# CPU_LPC1776.net
KiCad netlist of a schematic drawn in Altium Designer
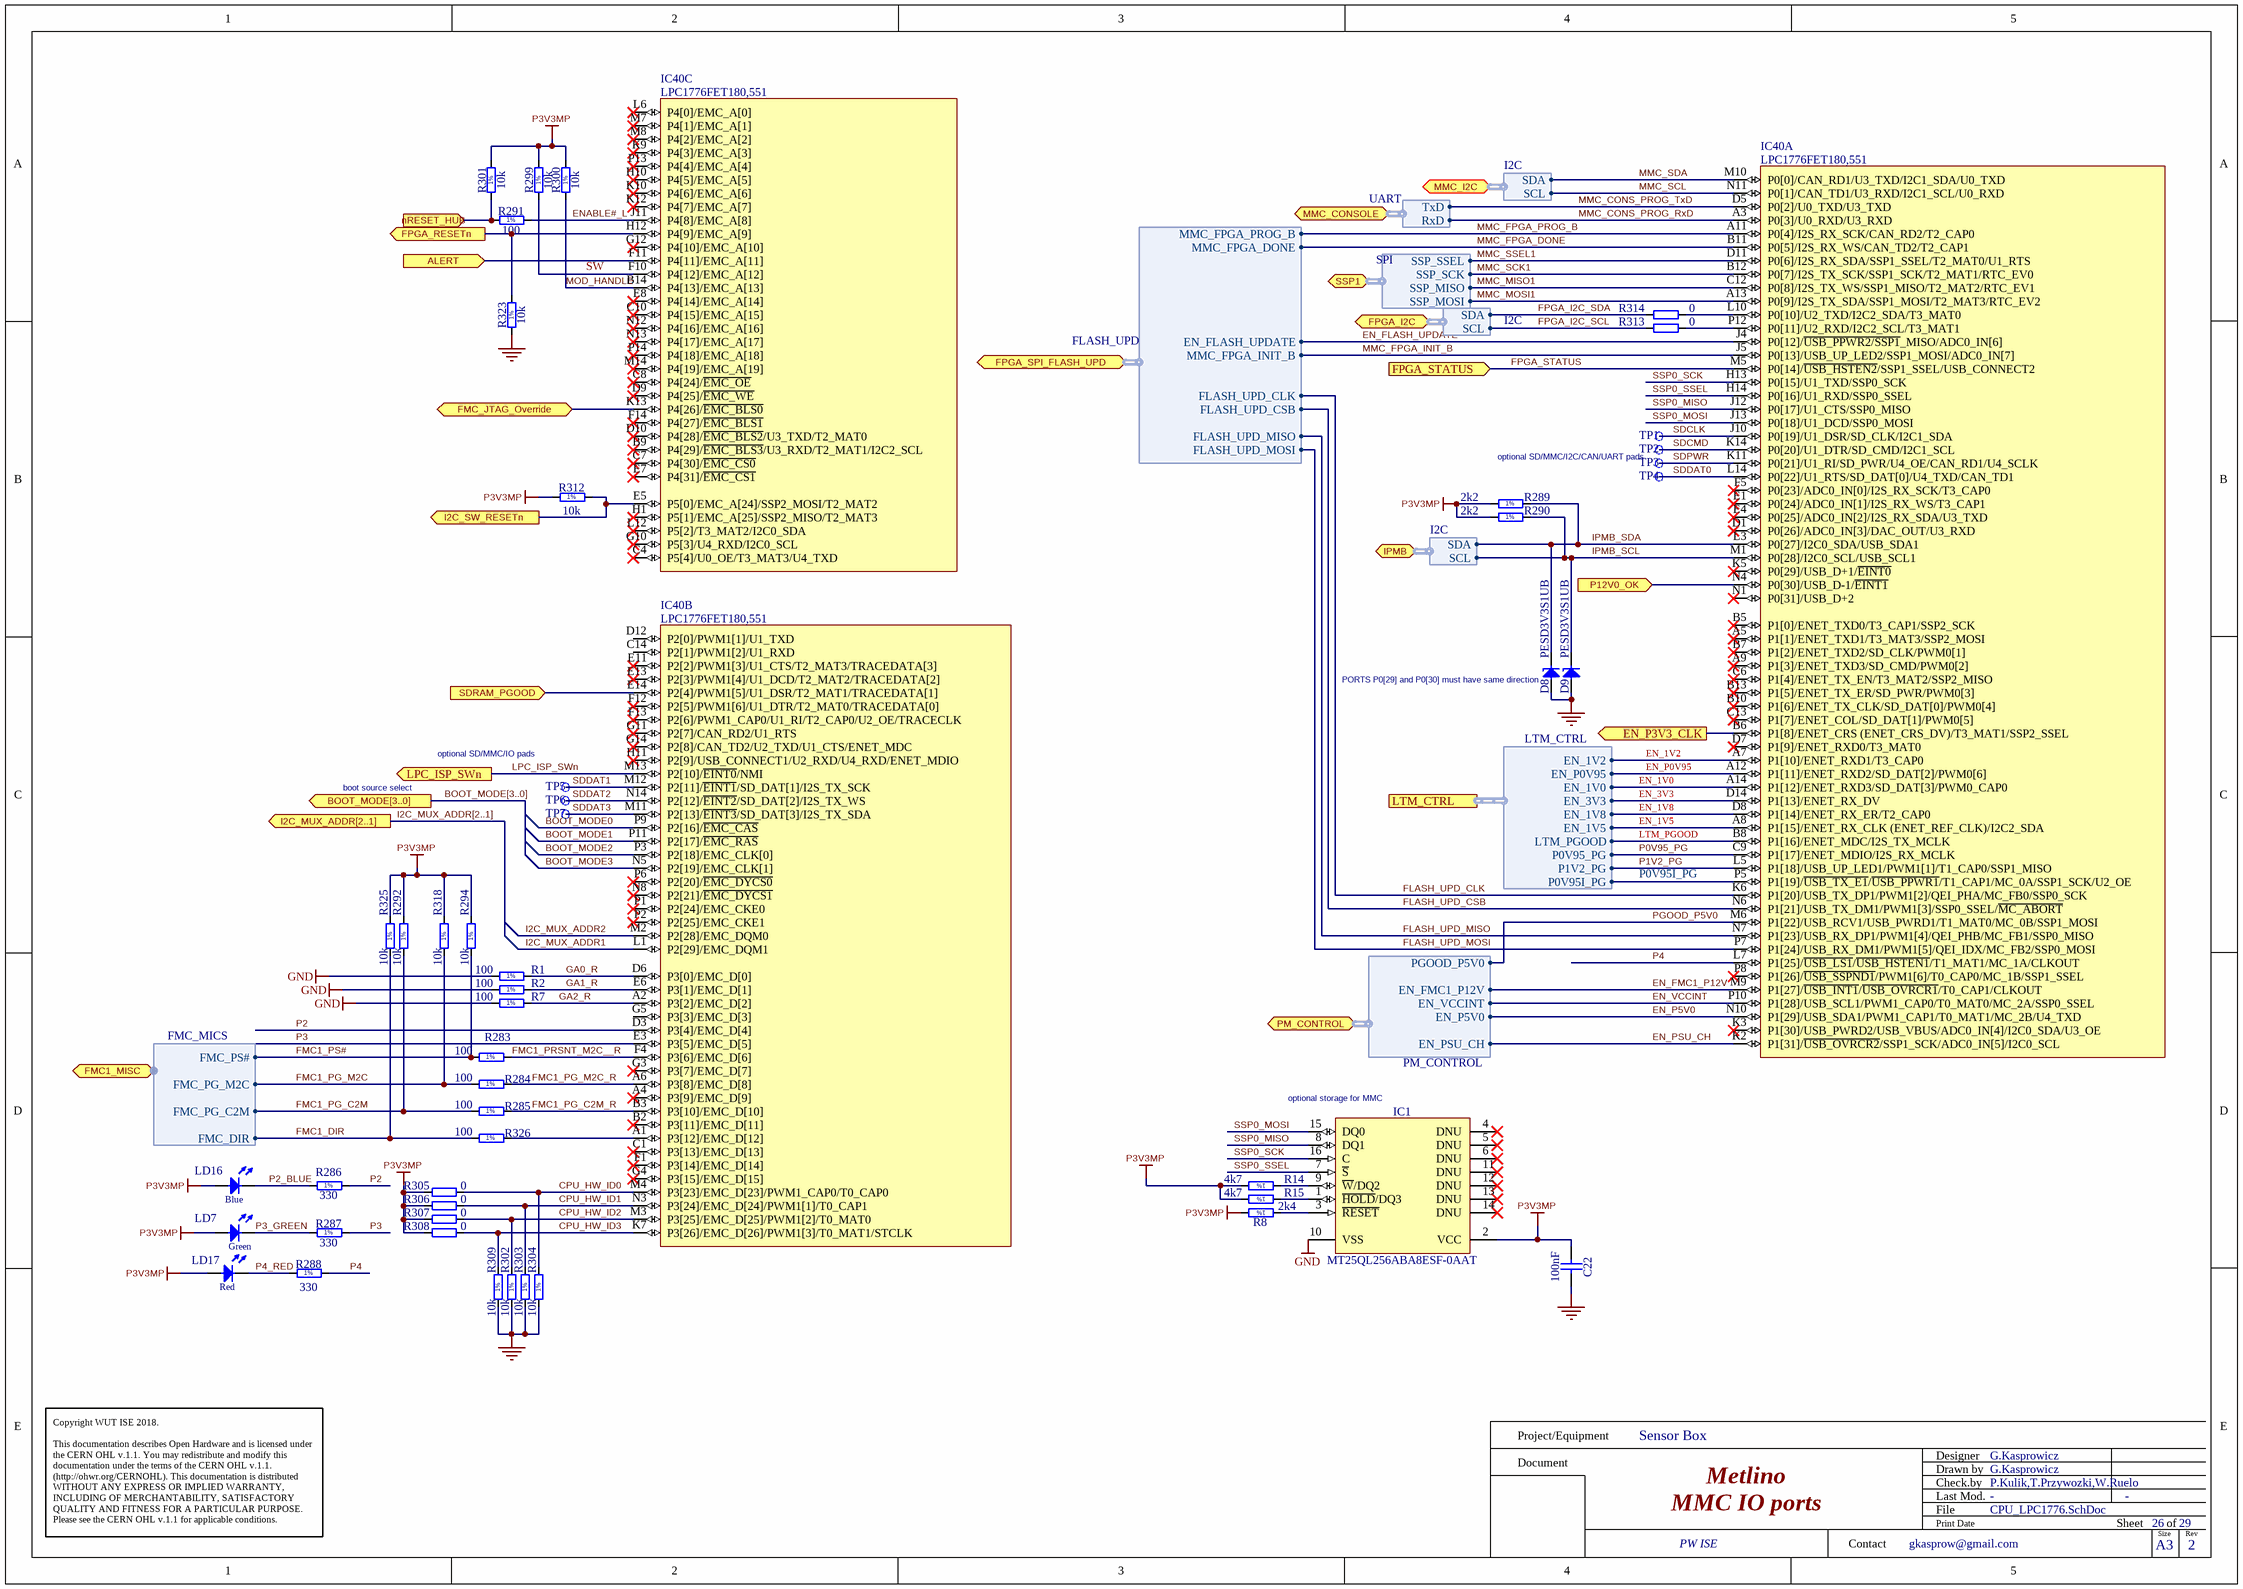
[diagram p0: CPU_LPC1776.SchDoc]

(export (version "E")
  (design (tool "Eeschema 10.0.6"))
  (components
    (comp (ref "C22")
      (value "100nF")
      (footprint "CAPC0603X33N")
      (description "Non-polarised capacitor")
      (fields
        (field (name "MANUFACTURER PART NUMBER") "CC0201_100NF_6.3V_10%_X5R")
        (field (name "MANUFACTURER") "GENERIC")
        (field (name "AUTHOR") "CERN DEM JLC")
      )
      (libsource (lib "Capacitors") (part "Capacitor - non polarized"))
    )
    (comp (ref "D8")
      (value "PESD3V3S1UB")
      (footprint "SODFL1608X65N")
      (description "ESD protection diode")
      (fields
        (field (name "MANUFACTURER") "NXP SEMICONDUCTORS")
        (field (name "VOLTAGE") "3V3")
        (field (name "AUTHOR") "CERN DEM JLC")
      )
      (libsource (lib "ICs And Semiconductors") (part "Diode ESD"))
    )
    (comp (ref "D9")
      (value "PESD3V3S1UB")
      (footprint "SODFL1608X65N")
      (description "ESD protection diode")
      (fields
        (field (name "MANUFACTURER") "NXP SEMICONDUCTORS")
        (field (name "VOLTAGE") "3V3")
        (field (name "AUTHOR") "CERN DEM JLC")
      )
      (libsource (lib "ICs And Semiconductors") (part "Diode ESD"))
    )
    (comp (ref "IC1")
      (value "MT25QL256ABA8ESF-0AAT")
      (footprint "SOIC127P1030X265-16N")
      (description "256Mbit (32MB), 2.7V-3.6V, Multiple I/O Serial NOR Flash Memory,with Reset# & Hold#")
      (fields (field (name "MANUFACTURER") "MICRON TECHNOLOGY") (field (name "AUTHOR") "CERN DEM JLC"))
      (libsource (lib "ICs And Semiconductors") (part "MT25QL256ABA8ESF"))
    )
    (comp (ref "IC40")
      (value "LPC1776FET180,551")
      (footprint "BGA180C80P14X14_1200X1200X120")
      (fields (field (name "MANUFACTURER") "NXP SEMICONDUCTORS") (field (name "AUTHOR") "CERN DEM JMW"))
      (libsource (lib "ICs And Semiconductors") (part "LPC1776FET180,551"))
    )
    (comp (ref "LD7")
      (value "Green")
      (footprint "LED_AVAGO_HSME-C120")
      (description "LED Green 1C 2A")
      (fields
        (field (name "MANUFACTURER PART NUMBER") "HSME-C120")
        (field (name "MANUFACTURER") "AVAGO TECHNOLOGIES")
        (field (name "AUTHOR") "CERN DEM JMW")
      )
      (libsource (lib "ICs And Semiconductors") (part "LED Green 1C 2A"))
    )
    (comp (ref "LD16")
      (value "Blue")
      (footprint "LED_AVAGO_HSMR-C120")
      (description "LED Blue 1C 2A")
      (fields
        (field (name "MANUFACTURER PART NUMBER") "HSMR-C120")
        (field (name "MANUFACTURER") "AVAGO TECHNOLOGIES")
        (field (name "AUTHOR") "CERN DEM JLC")
      )
      (libsource (lib "ICs And Semiconductors") (part "LED Blue 1C 2A"))
    )
    (comp (ref "LD17")
      (value "Red")
      (footprint "LED_KINGBRIGHT_KPH-1608SURCK")
      (description "LED Red 1C 2A")
      (fields
        (field (name "PART NUMBER") "LED_KINGBRIGHT_KPH-1608SURCK")
        (field (name "MANUFACTURER") "KINGBRIGHT")
        (field (name "AUTHOR") "CERN DEM JLC")
      )
      (libsource (lib "ICs And Semiconductors") (part "LED Red 1C 2A"))
    )
    (comp (ref "R1")
      (value "100")
      (footprint "RESC1005X40N")
      (description "Resistor - 1%")
      (fields
        (field (name "MANUFACTURER PART NUMBER") "R0402_100R_1%_0.1W_100PPM_50V")
        (field (name "MANUFACTURER") "GENERIC")
        (field (name "AUTHOR") "CERN DEM JLC")
      )
      (libsource (lib "Resistors") (part "Resistor - 1%"))
    )
    (comp (ref "R2")
      (value "100")
      (footprint "RESC1005X40N")
      (description "Resistor - 1%")
      (fields
        (field (name "MANUFACTURER PART NUMBER") "R0402_100R_1%_0.1W_100PPM_50V")
        (field (name "MANUFACTURER") "GENERIC")
        (field (name "AUTHOR") "CERN DEM JLC")
      )
      (libsource (lib "Resistors") (part "Resistor - 1%"))
    )
    (comp (ref "R7")
      (value "100")
      (footprint "RESC1005X40N")
      (description "Resistor - 1%")
      (fields
        (field (name "MANUFACTURER PART NUMBER") "R0402_100R_1%_0.1W_100PPM_50V")
        (field (name "MANUFACTURER") "GENERIC")
        (field (name "AUTHOR") "CERN DEM JLC")
      )
      (libsource (lib "Resistors") (part "Resistor - 1%"))
    )
    (comp (ref "R8")
      (value "2k4")
      (footprint "RESC1005X40N")
      (description "Resistor - 1%")
      (fields
        (field (name "MANUFACTURER PART NUMBER") "R0402_2K4_1%_0.0625W_100PPM")
        (field (name "MANUFACTURER") "GENERIC")
        (field (name "AUTHOR") "CERN DEM JLC")
      )
      (libsource (lib "Resistors") (part "Resistor - 1%"))
    )
    (comp (ref "R14")
      (value "4k7")
      (footprint "RESC1005X40N")
      (description "Resistor - 1%")
      (fields
        (field (name "MANUFACTURER PART NUMBER") "R0402_4K7_1%_0.0625W_100PPM")
        (field (name "MANUFACTURER") "GENERIC")
        (field (name "AUTHOR") "CERN DEM JLC")
      )
      (libsource (lib "Resistors") (part "Resistor - 1%"))
    )
    (comp (ref "R15")
      (value "4k7")
      (footprint "RESC1005X40N")
      (description "Resistor - 1%")
      (fields
        (field (name "MANUFACTURER PART NUMBER") "R0402_4K7_1%_0.0625W_100PPM")
        (field (name "MANUFACTURER") "GENERIC")
        (field (name "AUTHOR") "CERN DEM JLC")
      )
      (libsource (lib "Resistors") (part "Resistor - 1%"))
    )
    (comp (ref "R283")
      (value "100")
      (footprint "RESC1005X40N")
      (description "Resistor - 1%")
      (fields
        (field (name "MANUFACTURER PART NUMBER") "R0402_100R_1%_0.1W_100PPM_50V")
        (field (name "MANUFACTURER") "GENERIC")
        (field (name "AUTHOR") "CERN DEM JLC")
      )
      (libsource (lib "Resistors") (part "Resistor - 1%"))
    )
    (comp (ref "R284")
      (value "100")
      (footprint "RESC1005X40N")
      (description "Resistor - 1%")
      (fields
        (field (name "MANUFACTURER PART NUMBER") "R0402_100R_1%_0.1W_100PPM_50V")
        (field (name "MANUFACTURER") "GENERIC")
        (field (name "AUTHOR") "CERN DEM JLC")
      )
      (libsource (lib "Resistors") (part "Resistor - 1%"))
    )
    (comp (ref "R285")
      (value "100")
      (footprint "RESC1005X40N")
      (description "Resistor - 1%")
      (fields
        (field (name "MANUFACTURER PART NUMBER") "R0402_100R_1%_0.1W_100PPM_50V")
        (field (name "MANUFACTURER") "GENERIC")
        (field (name "AUTHOR") "CERN DEM JLC")
      )
      (libsource (lib "Resistors") (part "Resistor - 1%"))
    )
    (comp (ref "R286")
      (value "330")
      (footprint "RESC1005X40N")
      (description "Resistor - 1%")
      (fields
        (field (name "MANUFACTURER PART NUMBER") "R0402_330R_1%_0.0625W_100PPM")
        (field (name "MANUFACTURER") "GENERIC")
        (field (name "AUTHOR") "CERN DEM JLC")
      )
      (libsource (lib "Resistors") (part "Resistor - 1%"))
    )
    (comp (ref "R287")
      (value "330")
      (footprint "RESC1005X40N")
      (description "Resistor - 1%")
      (fields
        (field (name "MANUFACTURER PART NUMBER") "R0402_330R_1%_0.0625W_100PPM")
        (field (name "MANUFACTURER") "GENERIC")
        (field (name "AUTHOR") "CERN DEM JLC")
      )
      (libsource (lib "Resistors") (part "Resistor - 1%"))
    )
    (comp (ref "R288")
      (value "330")
      (footprint "RESC1005X40N")
      (description "Resistor - 1%")
      (fields
        (field (name "MANUFACTURER PART NUMBER") "R0402_330R_1%_0.0625W_100PPM")
        (field (name "MANUFACTURER") "GENERIC")
        (field (name "AUTHOR") "CERN DEM JLC")
      )
      (libsource (lib "Resistors") (part "Resistor - 1%"))
    )
    (comp (ref "R289")
      (value "2k2")
      (footprint "RESC1005X40N")
      (description "Resistor - 1%")
      (fields
        (field (name "MANUFACTURER PART NUMBER") "R0402_2K2_1%_0.0625W_100PPM")
        (field (name "MANUFACTURER") "GENERIC")
        (field (name "AUTHOR") "CERN DEM JLC")
      )
      (libsource (lib "Resistors") (part "Resistor - 1%"))
    )
    (comp (ref "R290")
      (value "2k2")
      (footprint "RESC1005X40N")
      (description "Resistor - 1%")
      (fields
        (field (name "MANUFACTURER PART NUMBER") "R0402_2K2_1%_0.0625W_100PPM")
        (field (name "MANUFACTURER") "GENERIC")
        (field (name "AUTHOR") "CERN DEM JLC")
      )
      (libsource (lib "Resistors") (part "Resistor - 1%"))
    )
    (comp (ref "R291")
      (value "100")
      (footprint "RESC1005X40N")
      (description "Resistor - 1%")
      (fields
        (field (name "MANUFACTURER PART NUMBER") "R0402_100R_1%_0.1W_100PPM_50V")
        (field (name "MANUFACTURER") "GENERIC")
        (field (name "AUTHOR") "CERN DEM JLC")
      )
      (libsource (lib "Resistors") (part "Resistor - 1%"))
    )
    (comp (ref "R292")
      (value "10k")
      (footprint "RESC1005X40N")
      (description "Resistor - 1%")
      (fields
        (field (name "MANUFACTURER PART NUMBER") "R0402_10K_1%_0.0625W_100PPM")
        (field (name "MANUFACTURER") "GENERIC")
        (field (name "AUTHOR") "CERN DEM JLC")
      )
      (libsource (lib "Resistors") (part "Resistor - 1%"))
    )
    (comp (ref "R294")
      (value "10k")
      (footprint "RESC1005X40N")
      (description "Resistor - 1%")
      (fields
        (field (name "MANUFACTURER PART NUMBER") "R0402_10K_1%_0.0625W_100PPM")
        (field (name "MANUFACTURER") "GENERIC")
        (field (name "AUTHOR") "CERN DEM JLC")
      )
      (libsource (lib "Resistors") (part "Resistor - 1%"))
    )
    (comp (ref "R299")
      (value "10k")
      (footprint "RESC1005X40N")
      (description "Resistor - 1%")
      (fields
        (field (name "MANUFACTURER PART NUMBER") "R0402_10K_1%_0.0625W_100PPM")
        (field (name "MANUFACTURER") "GENERIC")
        (field (name "AUTHOR") "CERN DEM JLC")
      )
      (libsource (lib "Resistors") (part "Resistor - 1%"))
    )
    (comp (ref "R300")
      (value "10k")
      (footprint "RESC1005X40N")
      (description "Resistor - 1%")
      (fields
        (field (name "MANUFACTURER PART NUMBER") "R0402_10K_1%_0.0625W_100PPM")
        (field (name "MANUFACTURER") "GENERIC")
        (field (name "AUTHOR") "CERN DEM JLC")
      )
      (libsource (lib "Resistors") (part "Resistor - 1%"))
    )
    (comp (ref "R301")
      (value "10k")
      (footprint "RESC1005X40N")
      (description "Resistor - 1%")
      (fields
        (field (name "MANUFACTURER PART NUMBER") "R0402_10K_1%_0.0625W_100PPM")
        (field (name "MANUFACTURER") "GENERIC")
        (field (name "AUTHOR") "CERN DEM JLC")
      )
      (libsource (lib "Resistors") (part "Resistor - 1%"))
    )
    (comp (ref "R302")
      (value "10k")
      (footprint "RESC1005X40N")
      (description "Resistor - 1%")
      (fields
        (field (name "MANUFACTURER PART NUMBER") "R0402_10K_1%_0.0625W_100PPM")
        (field (name "MANUFACTURER") "GENERIC")
        (field (name "AUTHOR") "CERN DEM JLC")
      )
      (libsource (lib "Resistors") (part "Resistor - 1%"))
    )
    (comp (ref "R303")
      (value "10k")
      (footprint "RESC1005X40N")
      (description "Resistor - 1%")
      (fields
        (field (name "MANUFACTURER PART NUMBER") "R0402_10K_1%_0.0625W_100PPM")
        (field (name "MANUFACTURER") "GENERIC")
        (field (name "AUTHOR") "CERN DEM JLC")
      )
      (libsource (lib "Resistors") (part "Resistor - 1%"))
    )
    (comp (ref "R304")
      (value "10k")
      (footprint "RESC1005X40N")
      (description "Resistor - 1%")
      (fields
        (field (name "MANUFACTURER PART NUMBER") "R0402_10K_1%_0.0625W_100PPM")
        (field (name "MANUFACTURER") "GENERIC")
        (field (name "AUTHOR") "CERN DEM JLC")
      )
      (libsource (lib "Resistors") (part "Resistor - 1%"))
    )
    (comp (ref "R305")
      (value "0")
      (footprint "RESC1005X40N")
      (description "Resistor")
      (fields
        (field (name "MANUFACTURER PART NUMBER") "R0402_0R_JUMPER")
        (field (name "MANUFACTURER") "GENERIC")
        (field (name "AUTHOR") "CERN DEM JLC")
      )
      (libsource (lib "Resistors") (part "Resistor"))
    )
    (comp (ref "R306")
      (value "0")
      (footprint "RESC1005X40N")
      (description "Resistor")
      (fields
        (field (name "MANUFACTURER PART NUMBER") "R0402_0R_JUMPER")
        (field (name "MANUFACTURER") "GENERIC")
        (field (name "AUTHOR") "CERN DEM JLC")
      )
      (libsource (lib "Resistors") (part "Resistor"))
    )
    (comp (ref "R307")
      (value "0")
      (footprint "RESC1005X40N")
      (description "Resistor")
      (fields
        (field (name "MANUFACTURER PART NUMBER") "R0402_0R_JUMPER")
        (field (name "MANUFACTURER") "GENERIC")
        (field (name "AUTHOR") "CERN DEM JLC")
      )
      (libsource (lib "Resistors") (part "Resistor"))
    )
    (comp (ref "R308")
      (value "0")
      (footprint "RESC1005X40N")
      (description "Resistor")
      (fields
        (field (name "MANUFACTURER PART NUMBER") "R0402_0R_JUMPER")
        (field (name "MANUFACTURER") "GENERIC")
        (field (name "AUTHOR") "CERN DEM JLC")
      )
      (libsource (lib "Resistors") (part "Resistor"))
    )
    (comp (ref "R309")
      (value "10k")
      (footprint "RESC1005X40N")
      (description "Resistor - 1%")
      (fields
        (field (name "MANUFACTURER PART NUMBER") "R0402_10K_1%_0.0625W_100PPM")
        (field (name "MANUFACTURER") "GENERIC")
        (field (name "AUTHOR") "CERN DEM JLC")
      )
      (libsource (lib "Resistors") (part "Resistor - 1%"))
    )
    (comp (ref "R312")
      (value "10k")
      (footprint "RESC1005X40N")
      (description "Resistor - 1%")
      (fields
        (field (name "MANUFACTURER PART NUMBER") "R0402_10K_1%_0.0625W_100PPM")
        (field (name "MANUFACTURER") "GENERIC")
        (field (name "AUTHOR") "CERN DEM JLC")
      )
      (libsource (lib "Resistors") (part "Resistor - 1%"))
    )
    (comp (ref "R313")
      (value "0")
      (footprint "RESC1005X40N")
      (description "Resistor")
      (fields
        (field (name "MANUFACTURER PART NUMBER") "R0402_0R_JUMPER")
        (field (name "MANUFACTURER") "GENERIC")
        (field (name "AUTHOR") "CERN DEM JLC")
      )
      (libsource (lib "Resistors") (part "Resistor"))
    )
    (comp (ref "R314")
      (value "0")
      (footprint "RESC1005X40N")
      (description "Resistor")
      (fields
        (field (name "MANUFACTURER PART NUMBER") "R0402_0R_JUMPER")
        (field (name "MANUFACTURER") "GENERIC")
        (field (name "AUTHOR") "CERN DEM JLC")
      )
      (libsource (lib "Resistors") (part "Resistor"))
    )
    (comp (ref "R318")
      (value "10k")
      (footprint "RESC1005X40N")
      (description "Resistor - 1%")
      (fields
        (field (name "MANUFACTURER PART NUMBER") "R0402_10K_1%_0.0625W_100PPM")
        (field (name "MANUFACTURER") "GENERIC")
        (field (name "AUTHOR") "CERN DEM JLC")
      )
      (libsource (lib "Resistors") (part "Resistor - 1%"))
    )
    (comp (ref "R323")
      (value "10k")
      (footprint "RESC1005X40N")
      (description "Resistor - 1%")
      (fields
        (field (name "MANUFACTURER PART NUMBER") "R0402_10K_1%_0.0625W_100PPM")
        (field (name "MANUFACTURER") "GENERIC")
        (field (name "AUTHOR") "CERN DEM JLC")
      )
      (libsource (lib "Resistors") (part "Resistor - 1%"))
    )
    (comp (ref "R325")
      (value "10k")
      (footprint "RESC1005X40N")
      (description "Resistor - 1%")
      (fields
        (field (name "MANUFACTURER PART NUMBER") "R0402_10K_1%_0.0625W_100PPM")
        (field (name "MANUFACTURER") "GENERIC")
        (field (name "AUTHOR") "CERN DEM JLC")
      )
      (libsource (lib "Resistors") (part "Resistor - 1%"))
    )
    (comp (ref "R326")
      (value "100")
      (footprint "RESC1005X40N")
      (description "Resistor - 1%")
      (fields
        (field (name "MANUFACTURER PART NUMBER") "R0402_100R_1%_0.1W_100PPM_50V")
        (field (name "MANUFACTURER") "GENERIC")
        (field (name "AUTHOR") "CERN DEM JLC")
      )
      (libsource (lib "Resistors") (part "Resistor - 1%"))
    )
    (comp (ref "TP1")
      (value "SMD_PAD_D1MM")
      (footprint "C100")
      (libsource (lib "altium-import") (part "root_0__*"))
    )
    (comp (ref "TP2")
      (value "SMD_PAD_D1MM")
      (footprint "C100")
      (libsource (lib "altium-import") (part "root_0__*"))
    )
    (comp (ref "TP3")
      (value "SMD_PAD_D1MM")
      (footprint "C100")
      (libsource (lib "altium-import") (part "root_0__*"))
    )
    (comp (ref "TP4")
      (value "SMD_PAD_D1MM")
      (footprint "C100")
      (libsource (lib "altium-import") (part "root_0__*"))
    )
    (comp (ref "TP5")
      (value "SMD_PAD_D1MM")
      (footprint "C100")
      (libsource (lib "altium-import") (part "root_0__*"))
    )
    (comp (ref "TP6")
      (value "SMD_PAD_D1MM")
      (footprint "C100")
      (libsource (lib "altium-import") (part "root_0__*"))
    )
    (comp (ref "TP7")
      (value "SMD_PAD_D1MM")
      (footprint "C100")
      (libsource (lib "altium-import") (part "root_0__*"))
    )
  )
  (nets
    (net (code "8") (name "/ALERT") (class "Default")
      (node (ref "IC40") (pin "F11") (pinfunction "P4[11]/EMC_A[11]_F11") (pintype "bidirectional"))
    )
    (net (code "9") (name "/BOOT_MODE0") (class "Default")
      (node (ref "IC40") (pin "P9") (pinfunction "P2[16]/~{EMC_CAS}_P9") (pintype "bidirectional"))
    )
    (net (code "10") (name "/BOOT_MODE1") (class "Default")
      (node (ref "IC40") (pin "P11") (pinfunction "P2[17]/~{EMC_RAS}_P11") (pintype "bidirectional"))
    )
    (net (code "11") (name "/BOOT_MODE2") (class "Default")
      (node (ref "IC40") (pin "P3") (pinfunction "P2[18]/EMC_CLK[0]_P3") (pintype "bidirectional"))
    )
    (net (code "12") (name "/BOOT_MODE3") (class "Default")
      (node (ref "IC40") (pin "N5") (pinfunction "P2[19]/EMC_CLK[1]_N5") (pintype "bidirectional"))
    )
    (net (code "14") (name "/CPU_HW_ID0") (class "Default")
      (node (ref "IC40") (pin "M4") (pinfunction "P3[23]/EMC_D[23]/PWM1_CAP0/T0_CAP0_M4") (pintype "bidirectional"))
      (node (ref "R304") (pin "2") (pinfunction "2_2") (pintype "passive"))
      (node (ref "R305") (pin "2") (pinfunction "2_2") (pintype "passive"))
    )
    (net (code "15") (name "/CPU_HW_ID1") (class "Default")
      (node (ref "IC40") (pin "N3") (pinfunction "P3[24]/EMC_D[24]/PWM1[1]/T0_CAP1_N3") (pintype "bidirectional"))
      (node (ref "R303") (pin "2") (pinfunction "2_2") (pintype "passive"))
      (node (ref "R306") (pin "2") (pinfunction "2_2") (pintype "passive"))
    )
    (net (code "16") (name "/CPU_HW_ID2") (class "Default")
      (node (ref "IC40") (pin "M3") (pinfunction "P3[25]/EMC_D[25]/PWM1[2]/T0_MAT0_M3") (pintype "bidirectional"))
      (node (ref "R302") (pin "2") (pinfunction "2_2") (pintype "passive"))
      (node (ref "R307") (pin "2") (pinfunction "2_2") (pintype "passive"))
    )
    (net (code "17") (name "/CPU_HW_ID3") (class "Default")
      (node (ref "IC40") (pin "K7") (pinfunction "P3[26]/EMC_D[26]/PWM1[3]/T0_MAT1/STCLK_K7") (pintype "bidirectional"))
      (node (ref "R308") (pin "2") (pinfunction "2_2") (pintype "passive"))
      (node (ref "R309") (pin "2") (pinfunction "2_2") (pintype "passive"))
    )
    (net (code "18") (name "/ENABLE#_L") (class "Default")
      (node (ref "IC40") (pin "J11") (pinfunction "P4[8]/EMC_A[8]_J11") (pintype "bidirectional"))
      (node (ref "R291") (pin "2") (pinfunction "2_2") (pintype "passive"))
    )
    (net (code "19") (name "/EN_1V0") (class "Default")
      (node (ref "IC40") (pin "A14") (pinfunction "P1[12]/ENET_RXD3/SD_DAT[3]/PWM0_CAP0_A14") (pintype "bidirectional"))
    )
    (net (code "20") (name "/EN_1V2") (class "Default")
      (node (ref "IC40") (pin "A7") (pinfunction "P1[10]/ENET_RXD1/T3_CAP0_A7") (pintype "bidirectional"))
    )
    (net (code "21") (name "/EN_1V5") (class "Default")
      (node (ref "IC40") (pin "A8") (pinfunction "P1[15]/ENET_RX_CLK_(ENET_REF_CLK)/I2C2_SDA_A8") (pintype "bidirectional"))
    )
    (net (code "22") (name "/EN_1V8") (class "Default")
      (node (ref "IC40") (pin "D8") (pinfunction "P1[14]/ENET_RX_ER/T2_CAP0_D8") (pintype "bidirectional"))
    )
    (net (code "23") (name "/EN_3V3") (class "Default")
      (node (ref "IC40") (pin "D14") (pinfunction "P1[13]/ENET_RX_DV_D14") (pintype "bidirectional"))
    )
    (net (code "24") (name "/EN_FLASH_UPDATE") (class "Default")
      (node (ref "IC40") (pin "J4") (pinfunction "P0[12]/~{USB_PPWR2/SSP1}_MISO/ADC0_IN[6]_J4") (pintype "bidirectional"))
    )
    (net (code "25") (name "/EN_FMC1_P12V") (class "Default")
      (node (ref "IC40") (pin "M9") (pinfunction "P1[27]/~{USB_INT1}/~{USB_OVRCR1}/T0_CAP1/CLKOUT_M9") (pintype "bidirectional"))
    )
    (net (code "26") (name "/EN_P0V95") (class "Default")
      (node (ref "IC40") (pin "A12") (pinfunction "P1[11]/ENET_RXD2/SD_DAT[2]/PWM0[6]_A12") (pintype "bidirectional"))
    )
    (net (code "27") (name "/EN_P3V3_CLK") (class "Default")
      (node (ref "IC40") (pin "B6") (pinfunction "P1[8]/ENET_CRS_(ENET_CRS_DV)/T3_MAT1/SSP2_SSEL_B6") (pintype "bidirectional"))
    )
    (net (code "28") (name "/EN_P5V0") (class "Default")
      (node (ref "IC40") (pin "N10") (pinfunction "P1[29]/USB_SDA1/PWM1_CAP1/T0_MAT1/MC_2B/U4_TXD_N10") (pintype "bidirectional"))
    )
    (net (code "29") (name "/EN_PSU_CH") (class "Default")
      (node (ref "IC40") (pin "K2") (pinfunction "P1[31]/~{USB_OVRCR2}/SSP1_SCK/ADC0_IN[5]/I2C0_SCL_K2") (pintype "bidirectional"))
    )
    (net (code "30") (name "/EN_VCCINT") (class "Default")
      (node (ref "IC40") (pin "P10") (pinfunction "P1[28]/USB_SCL1/PWM1_CAP0/T0_MAT0/MC_2A/SSP0_SSEL_P10") (pintype "bidirectional"))
    )
    (net (code "31") (name "/FLASH_UPD_CLK") (class "Default")
      (node (ref "IC40") (pin "K6") (pinfunction "P1[20]/USB_TX_DP1/PWM1[2]/QEI_PHA/MC_FB0/SSP0_SCK_K6") (pintype "bidirectional"))
    )
    (net (code "32") (name "/FLASH_UPD_CSB") (class "Default")
      (node (ref "IC40") (pin "N6") (pinfunction "P1[21]/USB_TX_DM1/PWM1[3]/SSP0_SSEL/~{MC_ABORT}_N6") (pintype "bidirectional"))
    )
    (net (code "33") (name "/FLASH_UPD_MISO") (class "Default")
      (node (ref "IC40") (pin "N7") (pinfunction "P1[23]/USB_RX_DP1/PWM1[4]/QEI_PHB/MC_FB1/SSP0_MISO_N7") (pintype "bidirectional"))
    )
    (net (code "34") (name "/FLASH_UPD_MOSI") (class "Default")
      (node (ref "IC40") (pin "P7") (pinfunction "P1[24]/USB_RX_DM1/PWM1[5]/QEI_IDX/MC_FB2/SSP0_MOSI_P7") (pintype "bidirectional"))
    )
    (net (code "35") (name "/FMC1_DIR") (class "Default")
      (node (ref "R325") (pin "1") (pinfunction "1_1") (pintype "passive"))
      (node (ref "R326") (pin "1") (pinfunction "1_1") (pintype "passive"))
    )
    (net (code "36") (name "/FMC1_PG_C2M") (class "Default")
      (node (ref "R285") (pin "1") (pinfunction "1_1") (pintype "passive"))
      (node (ref "R292") (pin "1") (pinfunction "1_1") (pintype "passive"))
    )
    (net (code "37") (name "/FMC1_PG_C2M_R") (class "Default")
      (node (ref "IC40") (pin "B3") (pinfunction "P3[10]/EMC_D[10]_B3") (pintype "bidirectional"))
      (node (ref "R285") (pin "2") (pinfunction "2_2") (pintype "passive"))
    )
    (net (code "38") (name "/FMC1_PG_M2C") (class "Default")
      (node (ref "R284") (pin "1") (pinfunction "1_1") (pintype "passive"))
      (node (ref "R318") (pin "1") (pinfunction "1_1") (pintype "passive"))
    )
    (net (code "39") (name "/FMC1_PG_M2C_R") (class "Default")
      (node (ref "IC40") (pin "A6") (pinfunction "P3[8]/EMC_D[8]_A6") (pintype "bidirectional"))
      (node (ref "R284") (pin "2") (pinfunction "2_2") (pintype "passive"))
    )
    (net (code "40") (name "/FMC1_PRSNT_M2C__R") (class "Default")
      (node (ref "IC40") (pin "F4") (pinfunction "P3[6]/EMC_D[6]_F4") (pintype "bidirectional"))
      (node (ref "R283") (pin "2") (pinfunction "2_2") (pintype "passive"))
    )
    (net (code "41") (name "/FMC1_PS#") (class "Default")
      (node (ref "R283") (pin "1") (pinfunction "1_1") (pintype "passive"))
      (node (ref "R294") (pin "1") (pinfunction "1_1") (pintype "passive"))
    )
    (net (code "42") (name "/FMC_JTAG_Override") (class "Default")
      (node (ref "IC40") (pin "K13") (pinfunction "P4[26]/~{EMC_BLS0}_K13") (pintype "bidirectional"))
    )
    (net (code "43") (name "/FPGA_I2C_SCL") (class "Default")
      (node (ref "R313") (pin "1") (pinfunction "1_1") (pintype "passive"))
    )
    (net (code "44") (name "/FPGA_I2C_SDA") (class "Default")
      (node (ref "R314") (pin "1") (pinfunction "1_1") (pintype "passive"))
    )
    (net (code "45") (name "/FPGA_RESETn") (class "Default")
      (node (ref "IC40") (pin "H12") (pinfunction "P4[9]/EMC_A[9]_H12") (pintype "bidirectional"))
      (node (ref "R323") (pin "2") (pinfunction "2_2") (pintype "passive"))
    )
    (net (code "46") (name "/FPGA_STATUS") (class "Default")
      (node (ref "IC40") (pin "M5") (pinfunction "P0[14]/~{USB_HSTEN2}/SSP1_SSEL/USB_CONNECT2_M5") (pintype "bidirectional"))
    )
    (net (code "47") (name "/GA0_R") (class "Default")
      (node (ref "IC40") (pin "D6") (pinfunction "P3[0]/EMC_D[0]_D6") (pintype "bidirectional"))
      (node (ref "R1") (pin "2") (pinfunction "2_2") (pintype "passive"))
    )
    (net (code "48") (name "/GA1_R") (class "Default")
      (node (ref "IC40") (pin "E6") (pinfunction "P3[1]/EMC_D[1]_E6") (pintype "bidirectional"))
      (node (ref "R2") (pin "2") (pinfunction "2_2") (pintype "passive"))
    )
    (net (code "49") (name "/GA2_R") (class "Default")
      (node (ref "IC40") (pin "A2") (pinfunction "P3[2]/EMC_D[2]_A2") (pintype "bidirectional"))
      (node (ref "R7") (pin "2") (pinfunction "2_2") (pintype "passive"))
    )
    (net (code "50") (name "/I2C_MUX_ADDR1") (class "Default")
      (node (ref "IC40") (pin "L1") (pinfunction "P2[29]/EMC_DQM1_L1") (pintype "bidirectional"))
    )
    (net (code "51") (name "/I2C_MUX_ADDR2") (class "Default")
      (node (ref "IC40") (pin "M2") (pinfunction "P2[28]/EMC_DQM0_M2") (pintype "bidirectional"))
    )
    (net (code "53") (name "/I2C_SW_RESETn") (class "Default")
      (node (ref "IC40") (pin "E5") (pinfunction "P5[0]/EMC_A[24]/SSP2_MOSI/T2_MAT2_E5") (pintype "bidirectional"))
      (node (ref "R312") (pin "2") (pinfunction "2_2") (pintype "passive"))
    )
    (net (code "54") (name "/IPMB_SCL") (class "Default")
      (node (ref "D9") (pin "1") (pinfunction "C_1") (pintype "passive"))
      (node (ref "IC40") (pin "M1") (pinfunction "P0[28]/I2C0_SCL/USB_SCL1_M1") (pintype "bidirectional"))
      (node (ref "R290") (pin "2") (pinfunction "2_2") (pintype "passive"))
    )
    (net (code "55") (name "/IPMB_SDA") (class "Default")
      (node (ref "D8") (pin "1") (pinfunction "C_1") (pintype "passive"))
      (node (ref "IC40") (pin "L3") (pinfunction "P0[27]/I2C0_SDA/USB_SDA1_L3") (pintype "bidirectional"))
      (node (ref "R289") (pin "2") (pinfunction "2_2") (pintype "passive"))
    )
    (net (code "56") (name "/LPC_ISP_SWn") (class "Default")
      (node (ref "IC40") (pin "M13") (pinfunction "P2[10]/~{EINT0}/NMI_M13") (pintype "bidirectional"))
    )
    (net (code "57") (name "/LTM_PGOOD") (class "Default")
      (node (ref "IC40") (pin "B8") (pinfunction "P1[16]/ENET_MDC/I2S_TX_MCLK_B8") (pintype "bidirectional"))
    )
    (net (code "58") (name "/MMC_CONS_PROG_RxD") (class "Default")
      (node (ref "IC40") (pin "A3") (pinfunction "P0[3]/U0_RXD/U3_RXD_A3") (pintype "bidirectional"))
    )
    (net (code "59") (name "/MMC_CONS_PROG_TxD") (class "Default")
      (node (ref "IC40") (pin "D5") (pinfunction "P0[2]/U0_TXD/U3_TXD_D5") (pintype "bidirectional"))
    )
    (net (code "60") (name "/MMC_FPGA_DONE") (class "Default")
      (node (ref "IC40") (pin "B11") (pinfunction "P0[5]/I2S_RX_WS/CAN_TD2/T2_CAP1_B11") (pintype "bidirectional"))
    )
    (net (code "61") (name "/MMC_FPGA_INIT_B") (class "Default")
      (node (ref "IC40") (pin "J5") (pinfunction "P0[13]/USB_UP_LED2/SSP1_MOSI/ADC0_IN[7]_J5") (pintype "bidirectional"))
    )
    (net (code "62") (name "/MMC_FPGA_PROG_B") (class "Default")
      (node (ref "IC40") (pin "A11") (pinfunction "P0[4]/I2S_RX_SCK/CAN_RD2/T2_CAP0_A11") (pintype "bidirectional"))
    )
    (net (code "63") (name "/MMC_MISO1") (class "Default")
      (node (ref "IC40") (pin "C12") (pinfunction "P0[8]/I2S_TX_WS/SSP1_MISO/T2_MAT2/RTC_EV1_C12") (pintype "bidirectional"))
    )
    (net (code "64") (name "/MMC_SCK1") (class "Default")
      (node (ref "IC40") (pin "B12") (pinfunction "P0[7]/I2S_TX_SCK/SSP1_SCK/T2_MAT1/RTC_EV0_B12") (pintype "bidirectional"))
    )
    (net (code "65") (name "/MMC_SCL") (class "Default")
      (node (ref "IC40") (pin "N11") (pinfunction "P0[1]/CAN_TD1/U3_RXD/I2C1_SCL/U0_RXD_N11") (pintype "bidirectional"))
    )
    (net (code "66") (name "/MMC_SDA") (class "Default")
      (node (ref "IC40") (pin "M10") (pinfunction "P0[0]/CAN_RD1/U3_TXD/I2C1_SDA/U0_TXD_M10") (pintype "bidirectional"))
    )
    (net (code "67") (name "/MMC_SSEL1") (class "Default")
      (node (ref "IC40") (pin "D11") (pinfunction "P0[6]/I2S_RX_SDA/SSP1_SSEL/T2_MAT0/U1_RTS_D11") (pintype "bidirectional"))
    )
    (net (code "68") (name "/MOD_HANDLE") (class "Default")
      (node (ref "IC40") (pin "B14") (pinfunction "P4[13]/EMC_A[13]_B14") (pintype "bidirectional"))
      (node (ref "R300") (pin "1") (pinfunction "1_1") (pintype "passive"))
    )
    (net (code "69") (name "/P0V95I_PG") (class "Default")
      (node (ref "IC40") (pin "P5") (pinfunction "P1[19]/~{USB_TX_E1}/~{USB_PPWR1}/T1_CAP1/MC_0A/SSP1_SCK/U2_OE_P5") (pintype "bidirectional"))
    )
    (net (code "70") (name "/P0V95_PG") (class "Default")
      (node (ref "IC40") (pin "C9") (pinfunction "P1[17]/ENET_MDIO/I2S_RX_MCLK_C9") (pintype "bidirectional"))
    )
    (net (code "71") (name "/P1V2_PG") (class "Default")
      (node (ref "IC40") (pin "L5") (pinfunction "P1[18]/USB_UP_LED1/PWM1[1]/T1_CAP0/SSP1_MISO_L5") (pintype "bidirectional"))
    )
    (net (code "72") (name "/P2") (class "Default")
      (node (ref "IC40") (pin "D3") (pinfunction "P3[4]/EMC_D[4]_D3") (pintype "bidirectional"))
      (node (ref "R286") (pin "2") (pinfunction "2_2") (pintype "passive"))
    )
    (net (code "73") (name "/P2_BLUE") (class "Default")
      (node (ref "LD16") (pin "1") (pinfunction "C_1") (pintype "passive"))
      (node (ref "R286") (pin "1") (pinfunction "1_1") (pintype "passive"))
    )
    (net (code "74") (name "/P3") (class "Default")
      (node (ref "IC40") (pin "E3") (pinfunction "P3[5]/EMC_D[5]_E3") (pintype "bidirectional"))
      (node (ref "R287") (pin "2") (pinfunction "2_2") (pintype "passive"))
    )
    (net (code "75") (name "/P3_GREEN") (class "Default")
      (node (ref "LD7") (pin "1") (pinfunction "C_1") (pintype "passive"))
      (node (ref "R287") (pin "1") (pinfunction "1_1") (pintype "passive"))
    )
    (net (code "76") (name "/P4") (class "Default")
      (node (ref "IC40") (pin "L7") (pinfunction "P1[25]/~{USB_LS1}/~{USB_HSTEN1}/T1_MAT1/MC_1A/CLKOUT_L7") (pintype "bidirectional"))
      (node (ref "R288") (pin "2") (pinfunction "2_2") (pintype "passive"))
    )
    (net (code "77") (name "/P4_RED") (class "Default")
      (node (ref "LD17") (pin "1") (pinfunction "C_1") (pintype "passive"))
      (node (ref "R288") (pin "1") (pinfunction "1_1") (pintype "passive"))
    )
    (net (code "78") (name "/P12V0_OK") (class "Default")
      (node (ref "IC40") (pin "N4") (pinfunction "P0[30]/USB_D-1/~{EINT1}_N4") (pintype "bidirectional"))
    )
    (net (code "79") (name "/PGOOD_P5V0") (class "Default")
      (node (ref "IC40") (pin "M6") (pinfunction "P1[22]/USB_RCV1/USB_PWRD1/T1_MAT0/MC_0B/SSP1_MOSI_M6") (pintype "bidirectional"))
    )
    (net (code "80") (name "/SDCLK") (class "Default")
      (node (ref "IC40") (pin "J10") (pinfunction "P0[19]/U1_DSR/SD_CLK/I2C1_SDA_J10") (pintype "bidirectional"))
      (node (ref "TP1") (pin "1") (pinfunction "1_1") (pintype "passive"))
    )
    (net (code "81") (name "/SDCMD") (class "Default")
      (node (ref "IC40") (pin "K14") (pinfunction "P0[20]/U1_DTR/SD_CMD/I2C1_SCL_K14") (pintype "bidirectional"))
      (node (ref "TP2") (pin "1") (pinfunction "1_1") (pintype "passive"))
    )
    (net (code "82") (name "/SDDAT0") (class "Default")
      (node (ref "IC40") (pin "L14") (pinfunction "P0[22]/U1_RTS/SD_DAT[0]/U4_TXD/CAN_TD1_L14") (pintype "bidirectional"))
      (node (ref "TP4") (pin "1") (pinfunction "1_1") (pintype "passive"))
    )
    (net (code "83") (name "/SDDAT1") (class "Default")
      (node (ref "IC40") (pin "M12") (pinfunction "P2[11]/~{EINT1}/SD_DAT[1]/I2S_TX_SCK_M12") (pintype "bidirectional"))
      (node (ref "TP5") (pin "1") (pinfunction "1_1") (pintype "passive"))
    )
    (net (code "84") (name "/SDDAT2") (class "Default")
      (node (ref "IC40") (pin "N14") (pinfunction "P2[12]/~{EINT2}/SD_DAT[2]/I2S_TX_WS_N14") (pintype "bidirectional"))
      (node (ref "TP6") (pin "1") (pinfunction "1_1") (pintype "passive"))
    )
    (net (code "85") (name "/SDDAT3") (class "Default")
      (node (ref "IC40") (pin "M11") (pinfunction "P2[13]/~{EINT3}/SD_DAT[3]/I2S_TX_SDA_M11") (pintype "bidirectional"))
      (node (ref "TP7") (pin "1") (pinfunction "1_1") (pintype "passive"))
    )
    (net (code "86") (name "/SDPWR") (class "Default")
      (node (ref "IC40") (pin "K11") (pinfunction "P0[21]/U1_RI/SD_PWR/U4_OE/CAN_RD1/U4_SCLK_K11") (pintype "bidirectional"))
      (node (ref "TP3") (pin "1") (pinfunction "1_1") (pintype "passive"))
    )
    (net (code "87") (name "/SDRAM_PGOOD") (class "Default")
      (node (ref "IC40") (pin "E14") (pinfunction "P2[4]/PWM1[5]/U1_DSR/T2_MAT1/TRACEDATA[1]_E14") (pintype "bidirectional"))
    )
    (net (code "88") (name "/SSP0_MISO") (class "Default")
      (node (ref "IC1") (pin "8") (pinfunction "DQ1_8") (pintype "bidirectional"))
      (node (ref "IC40") (pin "J12") (pinfunction "P0[17]/U1_CTS/SSP0_MISO_J12") (pintype "bidirectional"))
    )
    (net (code "89") (name "/SSP0_MOSI") (class "Default")
      (node (ref "IC1") (pin "15") (pinfunction "DQ0_15") (pintype "bidirectional"))
      (node (ref "IC40") (pin "J13") (pinfunction "P0[18]/U1_DCD/SSP0_MOSI_J13") (pintype "bidirectional"))
    )
    (net (code "90") (name "/SSP0_SCK") (class "Default")
      (node (ref "IC1") (pin "16") (pinfunction "C_16") (pintype "input"))
      (node (ref "IC40") (pin "H13") (pinfunction "P0[15]/U1_TXD/SSP0_SCK_H13") (pintype "bidirectional"))
    )
    (net (code "91") (name "/SSP0_SSEL") (class "Default")
      (node (ref "IC1") (pin "7") (pinfunction "~{S}_7") (pintype "input"))
      (node (ref "IC40") (pin "H14") (pinfunction "P0[16]/U1_RXD/SSP0_SSEL_H14") (pintype "bidirectional"))
    )
    (net (code "92") (name "/SW") (class "Default")
      (node (ref "IC40") (pin "F10") (pinfunction "P4[12]/EMC_A[12]_F10") (pintype "bidirectional"))
      (node (ref "R299") (pin "1") (pinfunction "1_1") (pintype "passive"))
    )
    (net (code "93") (name "/nRESET_HUB") (class "Default")
      (node (ref "R291") (pin "1") (pinfunction "1_1") (pintype "passive"))
      (node (ref "R301") (pin "1") (pinfunction "1_1") (pintype "passive"))
    )
    (net (code "96") (name "/{I2C}") (class "Default")
      (node (ref "IC40") (pin "A13") (pinfunction "P0[9]/I2S_TX_SDA/SSP1_MOSI/T2_MAT3/RTC_EV2_A13") (pintype "bidirectional"))
    )
    (net (code "101") (name "GND") (class "Default")
      (node (ref "C22") (pin "1") (pinfunction "1_1") (pintype "passive"))
      (node (ref "D8") (pin "2") (pinfunction "A_2") (pintype "passive"))
      (node (ref "D9") (pin "2") (pinfunction "A_2") (pintype "passive"))
      (node (ref "IC1") (pin "10") (pinfunction "VSS_10") (pintype "power_in"))
      (node (ref "R1") (pin "1") (pinfunction "1_1") (pintype "passive"))
      (node (ref "R2") (pin "1") (pinfunction "1_1") (pintype "passive"))
      (node (ref "R302") (pin "1") (pinfunction "1_1") (pintype "passive"))
      (node (ref "R303") (pin "1") (pinfunction "1_1") (pintype "passive"))
      (node (ref "R304") (pin "1") (pinfunction "1_1") (pintype "passive"))
      (node (ref "R309") (pin "1") (pinfunction "1_1") (pintype "passive"))
      (node (ref "R323") (pin "1") (pinfunction "1_1") (pintype "passive"))
      (node (ref "R7") (pin "1") (pinfunction "1_1") (pintype "passive"))
    )
    (net (code "102") (name "Net-(IC1-~{HOLD}{slash}DQ3)") (class "Default")
      (node (ref "IC1") (pin "1") (pinfunction "~{HOLD}/DQ3_1") (pintype "bidirectional"))
      (node (ref "R15") (pin "1") (pinfunction "1_1") (pintype "passive"))
    )
    (net (code "103") (name "Net-(IC1-~{RESET})") (class "Default")
      (node (ref "IC1") (pin "3") (pinfunction "~{RESET}_3") (pintype "input"))
      (node (ref "R8") (pin "1") (pinfunction "1_1") (pintype "passive"))
    )
    (net (code "104") (name "Net-(IC1-~{W}{slash}DQ2)") (class "Default")
      (node (ref "IC1") (pin "9") (pinfunction "~{W}/DQ2_9") (pintype "bidirectional"))
      (node (ref "R14") (pin "1") (pinfunction "1_1") (pintype "passive"))
    )
    (net (code "105") (name "Net-(IC40A-P0[10]{slash}U2_TXD{slash}I2C2_SDA{slash}T3_MAT0)") (class "Default")
      (node (ref "IC40") (pin "L10") (pinfunction "P0[10]/U2_TXD/I2C2_SDA/T3_MAT0_L10") (pintype "bidirectional"))
      (node (ref "R314") (pin "2") (pinfunction "2_2") (pintype "passive"))
    )
    (net (code "106") (name "Net-(IC40A-P0[11]{slash}U2_RXD{slash}I2C2_SCL{slash}T3_MAT1)") (class "Default")
      (node (ref "IC40") (pin "P12") (pinfunction "P0[11]/U2_RXD/I2C2_SCL/T3_MAT1_P12") (pintype "bidirectional"))
      (node (ref "R313") (pin "2") (pinfunction "2_2") (pintype "passive"))
    )
    (net (code "107") (name "Net-(IC40B-P3[12]{slash}EMC_D[12])") (class "Default")
      (node (ref "IC40") (pin "A1") (pinfunction "P3[12]/EMC_D[12]_A1") (pintype "bidirectional"))
      (node (ref "R326") (pin "2") (pinfunction "2_2") (pintype "passive"))
    )
    (net (code "108") (name "P3V3MP") (class "Default")
      (node (ref "C22") (pin "2") (pinfunction "2_2") (pintype "passive"))
      (node (ref "IC1") (pin "2") (pinfunction "VCC_2") (pintype "power_in"))
      (node (ref "LD16") (pin "2") (pinfunction "A_2") (pintype "passive"))
      (node (ref "LD17") (pin "2") (pinfunction "A_2") (pintype "passive"))
      (node (ref "LD7") (pin "2") (pinfunction "A_2") (pintype "passive"))
      (node (ref "R14") (pin "2") (pinfunction "2_2") (pintype "passive"))
      (node (ref "R15") (pin "2") (pinfunction "2_2") (pintype "passive"))
      (node (ref "R289") (pin "1") (pinfunction "1_1") (pintype "passive"))
      (node (ref "R290") (pin "1") (pinfunction "1_1") (pintype "passive"))
      (node (ref "R292") (pin "2") (pinfunction "2_2") (pintype "passive"))
      (node (ref "R294") (pin "2") (pinfunction "2_2") (pintype "passive"))
      (node (ref "R299") (pin "2") (pinfunction "2_2") (pintype "passive"))
      (node (ref "R300") (pin "2") (pinfunction "2_2") (pintype "passive"))
      (node (ref "R301") (pin "2") (pinfunction "2_2") (pintype "passive"))
      (node (ref "R305") (pin "1") (pinfunction "1_1") (pintype "passive"))
      (node (ref "R306") (pin "1") (pinfunction "1_1") (pintype "passive"))
      (node (ref "R307") (pin "1") (pinfunction "1_1") (pintype "passive"))
      (node (ref "R308") (pin "1") (pinfunction "1_1") (pintype "passive"))
      (node (ref "R312") (pin "1") (pinfunction "1_1") (pintype "passive"))
      (node (ref "R318") (pin "2") (pinfunction "2_2") (pintype "passive"))
      (node (ref "R325") (pin "2") (pinfunction "2_2") (pintype "passive"))
      (node (ref "R8") (pin "2") (pinfunction "2_2") (pintype "passive"))
    )
    (net (code "109") (name "unconnected-(IC1-DNU-Pad4)") (class "Default")
      (node (ref "IC1") (pin "4") (pinfunction "DNU_4") (pintype "passive+no_connect"))
    )
    (net (code "110") (name "unconnected-(IC1-DNU-Pad5)") (class "Default")
      (node (ref "IC1") (pin "5") (pinfunction "DNU_5") (pintype "passive+no_connect"))
    )
    (net (code "111") (name "unconnected-(IC1-DNU-Pad6)") (class "Default")
      (node (ref "IC1") (pin "6") (pinfunction "DNU_6") (pintype "passive+no_connect"))
    )
    (net (code "112") (name "unconnected-(IC1-DNU-Pad11)") (class "Default")
      (node (ref "IC1") (pin "11") (pinfunction "DNU_11") (pintype "passive+no_connect"))
    )
    (net (code "113") (name "unconnected-(IC1-DNU-Pad12)") (class "Default")
      (node (ref "IC1") (pin "12") (pinfunction "DNU_12") (pintype "passive+no_connect"))
    )
    (net (code "114") (name "unconnected-(IC1-DNU-Pad13)") (class "Default")
      (node (ref "IC1") (pin "13") (pinfunction "DNU_13") (pintype "passive+no_connect"))
    )
    (net (code "115") (name "unconnected-(IC1-DNU-Pad14)") (class "Default")
      (node (ref "IC1") (pin "14") (pinfunction "DNU_14") (pintype "passive+no_connect"))
    )
    (net (code "116") (name "unconnected-(IC40A-P0[23]{slash}ADC0_IN[0]{slash}I2S_RX_SCK{slash}T3_CAP0-PadF5)") (class "Default")
      (node (ref "IC40") (pin "F5") (pinfunction "P0[23]/ADC0_IN[0]/I2S_RX_SCK/T3_CAP0_F5") (pintype "bidirectional+no_connect"))
    )
    (net (code "117") (name "unconnected-(IC40A-P0[24]{slash}ADC0_IN[1]{slash}I2S_RX_WS{slash}T3_CAP1-PadE1)") (class "Default")
      (node (ref "IC40") (pin "E1") (pinfunction "P0[24]/ADC0_IN[1]/I2S_RX_WS/T3_CAP1_E1") (pintype "bidirectional+no_connect"))
    )
    (net (code "118") (name "unconnected-(IC40A-P0[25]{slash}ADC0_IN[2]{slash}I2S_RX_SDA{slash}U3_TXD-PadE4)") (class "Default")
      (node (ref "IC40") (pin "E4") (pinfunction "P0[25]/ADC0_IN[2]/I2S_RX_SDA/U3_TXD_E4") (pintype "bidirectional+no_connect"))
    )
    (net (code "119") (name "unconnected-(IC40A-P0[26]{slash}ADC0_IN[3]{slash}DAC_OUT{slash}U3_RXD-PadD1)") (class "Default")
      (node (ref "IC40") (pin "D1") (pinfunction "P0[26]/ADC0_IN[3]/DAC_OUT/U3_RXD_D1") (pintype "bidirectional+no_connect"))
    )
    (net (code "120") (name "unconnected-(IC40A-P0[29]{slash}USB_D+1{slash}~{EINT0}-PadK5)") (class "Default")
      (node (ref "IC40") (pin "K5") (pinfunction "P0[29]/USB_D+1/~{EINT0}_K5") (pintype "bidirectional+no_connect"))
    )
    (net (code "121") (name "unconnected-(IC40A-P0[31]{slash}USB_D+2-PadN1)") (class "Default")
      (node (ref "IC40") (pin "N1") (pinfunction "P0[31]/USB_D+2_N1") (pintype "bidirectional+no_connect"))
    )
    (net (code "122") (name "unconnected-(IC40A-P1[0]{slash}ENET_TXD0{slash}T3_CAP1{slash}SSP2_SCK-PadB5)") (class "Default")
      (node (ref "IC40") (pin "B5") (pinfunction "P1[0]/ENET_TXD0/T3_CAP1/SSP2_SCK_B5") (pintype "bidirectional+no_connect"))
    )
    (net (code "123") (name "unconnected-(IC40A-P1[1]{slash}ENET_TXD1{slash}T3_MAT3{slash}SSP2_MOSI-PadA5)") (class "Default")
      (node (ref "IC40") (pin "A5") (pinfunction "P1[1]/ENET_TXD1/T3_MAT3/SSP2_MOSI_A5") (pintype "bidirectional+no_connect"))
    )
    (net (code "124") (name "unconnected-(IC40A-P1[2]{slash}ENET_TXD2{slash}SD_CLK{slash}PWM0[1]-PadB7)") (class "Default")
      (node (ref "IC40") (pin "B7") (pinfunction "P1[2]/ENET_TXD2/SD_CLK/PWM0[1]_B7") (pintype "bidirectional+no_connect"))
    )
    (net (code "125") (name "unconnected-(IC40A-P1[3]{slash}ENET_TXD3{slash}SD_CMD{slash}PWM0[2]-PadA9)") (class "Default")
      (node (ref "IC40") (pin "A9") (pinfunction "P1[3]/ENET_TXD3/SD_CMD/PWM0[2]_A9") (pintype "bidirectional+no_connect"))
    )
    (net (code "126") (name "unconnected-(IC40A-P1[4]{slash}ENET_TX_EN{slash}T3_MAT2{slash}SSP2_MISO-PadC6)") (class "Default")
      (node (ref "IC40") (pin "C6") (pinfunction "P1[4]/ENET_TX_EN/T3_MAT2/SSP2_MISO_C6") (pintype "bidirectional+no_connect"))
    )
    (net (code "127") (name "unconnected-(IC40A-P1[5]{slash}ENET_TX_ER{slash}SD_PWR{slash}PWM0[3]-PadB13)") (class "Default")
      (node (ref "IC40") (pin "B13") (pinfunction "P1[5]/ENET_TX_ER/SD_PWR/PWM0[3]_B13") (pintype "bidirectional+no_connect"))
    )
    (net (code "128") (name "unconnected-(IC40A-P1[6]{slash}ENET_TX_CLK{slash}SD_DAT[0]{slash}PWM0[4]-PadB10)") (class "Default")
      (node (ref "IC40") (pin "B10") (pinfunction "P1[6]/ENET_TX_CLK/SD_DAT[0]/PWM0[4]_B10") (pintype "bidirectional+no_connect"))
    )
    (net (code "129") (name "unconnected-(IC40A-P1[7]{slash}ENET_COL{slash}SD_DAT[1]{slash}PWM0[5]-PadC13)") (class "Default")
      (node (ref "IC40") (pin "C13") (pinfunction "P1[7]/ENET_COL/SD_DAT[1]/PWM0[5]_C13") (pintype "bidirectional+no_connect"))
    )
    (net (code "130") (name "unconnected-(IC40A-P1[9]{slash}ENET_RXD0{slash}T3_MAT0-PadD7)") (class "Default")
      (node (ref "IC40") (pin "D7") (pinfunction "P1[9]/ENET_RXD0/T3_MAT0_D7") (pintype "bidirectional+no_connect"))
    )
    (net (code "131") (name "unconnected-(IC40A-P1[26]{slash}~{USB_SSPND1}{slash}PWM1[6]{slash}T0_CAP0{slash}MC_1B{slash}SSP1_SSEL-PadP8)") (class "Default")
      (node (ref "IC40") (pin "P8") (pinfunction "P1[26]/~{USB_SSPND1}/PWM1[6]/T0_CAP0/MC_1B/SSP1_SSEL_P8") (pintype "bidirectional+no_connect"))
    )
    (net (code "132") (name "unconnected-(IC40A-P1[30]{slash}USB_PWRD2{slash}USB_VBUS{slash}ADC0_IN[4]{slash}I2C0_SDA{slash}U3_OE-PadK3)") (class "Default")
      (node (ref "IC40") (pin "K3") (pinfunction "P1[30]/USB_PWRD2/USB_VBUS/ADC0_IN[4]/I2C0_SDA/U3_OE_K3") (pintype "bidirectional+no_connect"))
    )
    (net (code "133") (name "unconnected-(IC40B-P2[0]{slash}PWM1[1]{slash}U1_TXD-PadD12)") (class "Default")
      (node (ref "IC40") (pin "D12") (pinfunction "P2[0]/PWM1[1]/U1_TXD_D12") (pintype "bidirectional"))
    )
    (net (code "134") (name "unconnected-(IC40B-P2[1]{slash}PWM1[2]{slash}U1_RXD-PadC14)") (class "Default")
      (node (ref "IC40") (pin "C14") (pinfunction "P2[1]/PWM1[2]/U1_RXD_C14") (pintype "bidirectional"))
    )
    (net (code "135") (name "unconnected-(IC40B-P2[2]{slash}PWM1[3]{slash}U1_CTS{slash}T2_MAT3{slash}TRACEDATA[3]-PadE11)") (class "Default")
      (node (ref "IC40") (pin "E11") (pinfunction "P2[2]/PWM1[3]/U1_CTS/T2_MAT3/TRACEDATA[3]_E11") (pintype "bidirectional+no_connect"))
    )
    (net (code "136") (name "unconnected-(IC40B-P2[3]{slash}PWM1[4]{slash}U1_DCD{slash}T2_MAT2{slash}TRACEDATA[2]-PadE13)") (class "Default")
      (node (ref "IC40") (pin "E13") (pinfunction "P2[3]/PWM1[4]/U1_DCD/T2_MAT2/TRACEDATA[2]_E13") (pintype "bidirectional+no_connect"))
    )
    (net (code "137") (name "unconnected-(IC40B-P2[5]{slash}PWM1[6]{slash}U1_DTR{slash}T2_MAT0{slash}TRACEDATA[0]-PadF12)") (class "Default")
      (node (ref "IC40") (pin "F12") (pinfunction "P2[5]/PWM1[6]/U1_DTR/T2_MAT0/TRACEDATA[0]_F12") (pintype "bidirectional+no_connect"))
    )
    (net (code "138") (name "unconnected-(IC40B-P2[6]{slash}PWM1_CAP0{slash}U1_RI{slash}T2_CAP0{slash}U2_OE{slash}TRACECLK-PadF13)") (class "Default")
      (node (ref "IC40") (pin "F13") (pinfunction "P2[6]/PWM1_CAP0/U1_RI/T2_CAP0/U2_OE/TRACECLK_F13") (pintype "bidirectional+no_connect"))
    )
    (net (code "139") (name "unconnected-(IC40B-P2[7]{slash}CAN_RD2{slash}U1_RTS-PadG11)") (class "Default")
      (node (ref "IC40") (pin "G11") (pinfunction "P2[7]/CAN_RD2/U1_RTS_G11") (pintype "bidirectional+no_connect"))
    )
    (net (code "140") (name "unconnected-(IC40B-P2[8]{slash}CAN_TD2{slash}U2_TXD{slash}U1_CTS{slash}ENET_MDC-PadG14)") (class "Default")
      (node (ref "IC40") (pin "G14") (pinfunction "P2[8]/CAN_TD2/U2_TXD/U1_CTS/ENET_MDC_G14") (pintype "bidirectional+no_connect"))
    )
    (net (code "141") (name "unconnected-(IC40B-P2[9]{slash}USB_CONNECT1{slash}U2_RXD{slash}U4_RXD{slash}ENET_MDIO-PadH11)") (class "Default")
      (node (ref "IC40") (pin "H11") (pinfunction "P2[9]/USB_CONNECT1/U2_RXD/U4_RXD/ENET_MDIO_H11") (pintype "bidirectional+no_connect"))
    )
    (net (code "142") (name "unconnected-(IC40B-P2[20]{slash}~{EMC_DYCS0}-PadP6)") (class "Default")
      (node (ref "IC40") (pin "P6") (pinfunction "P2[20]/~{EMC_DYCS0}_P6") (pintype "bidirectional+no_connect"))
    )
    (net (code "143") (name "unconnected-(IC40B-P2[21]{slash}~{EMC_DYCS1}-PadN8)") (class "Default")
      (node (ref "IC40") (pin "N8") (pinfunction "P2[21]/~{EMC_DYCS1}_N8") (pintype "bidirectional+no_connect"))
    )
    (net (code "144") (name "unconnected-(IC40B-P2[24]{slash}EMC_CKE0-PadP1)") (class "Default")
      (node (ref "IC40") (pin "P1") (pinfunction "P2[24]/EMC_CKE0_P1") (pintype "bidirectional+no_connect"))
    )
    (net (code "145") (name "unconnected-(IC40B-P2[25]{slash}EMC_CKE1-PadP2)") (class "Default")
      (node (ref "IC40") (pin "P2") (pinfunction "P2[25]/EMC_CKE1_P2") (pintype "bidirectional+no_connect"))
    )
    (net (code "146") (name "unconnected-(IC40B-P3[3]{slash}EMC_D[3]-PadG5)") (class "Default")
      (node (ref "IC40") (pin "G5") (pinfunction "P3[3]/EMC_D[3]_G5") (pintype "bidirectional"))
    )
    (net (code "147") (name "unconnected-(IC40B-P3[7]{slash}EMC_D[7]-PadG3)") (class "Default")
      (node (ref "IC40") (pin "G3") (pinfunction "P3[7]/EMC_D[7]_G3") (pintype "bidirectional+no_connect"))
    )
    (net (code "148") (name "unconnected-(IC40B-P3[9]{slash}EMC_D[9]-PadA4)") (class "Default")
      (node (ref "IC40") (pin "A4") (pinfunction "P3[9]/EMC_D[9]_A4") (pintype "bidirectional+no_connect"))
    )
    (net (code "149") (name "unconnected-(IC40B-P3[11]{slash}EMC_D[11]-PadB2)") (class "Default")
      (node (ref "IC40") (pin "B2") (pinfunction "P3[11]/EMC_D[11]_B2") (pintype "bidirectional+no_connect"))
    )
    (net (code "150") (name "unconnected-(IC40B-P3[13]{slash}EMC_D[13]-PadC1)") (class "Default")
      (node (ref "IC40") (pin "C1") (pinfunction "P3[13]/EMC_D[13]_C1") (pintype "bidirectional+no_connect"))
    )
    (net (code "151") (name "unconnected-(IC40B-P3[14]{slash}EMC_D[14]-PadF1)") (class "Default")
      (node (ref "IC40") (pin "F1") (pinfunction "P3[14]/EMC_D[14]_F1") (pintype "bidirectional+no_connect"))
    )
    (net (code "152") (name "unconnected-(IC40B-P3[15]{slash}EMC_D[15]-PadG4)") (class "Default")
      (node (ref "IC40") (pin "G4") (pinfunction "P3[15]/EMC_D[15]_G4") (pintype "bidirectional+no_connect"))
    )
    (net (code "153") (name "unconnected-(IC40C-P4[0]{slash}EMC_A[0]-PadL6)") (class "Default")
      (node (ref "IC40") (pin "L6") (pinfunction "P4[0]/EMC_A[0]_L6") (pintype "bidirectional+no_connect"))
    )
    (net (code "154") (name "unconnected-(IC40C-P4[1]{slash}EMC_A[1]-PadM7)") (class "Default")
      (node (ref "IC40") (pin "M7") (pinfunction "P4[1]/EMC_A[1]_M7") (pintype "bidirectional+no_connect"))
    )
    (net (code "155") (name "unconnected-(IC40C-P4[2]{slash}EMC_A[2]-PadM8)") (class "Default")
      (node (ref "IC40") (pin "M8") (pinfunction "P4[2]/EMC_A[2]_M8") (pintype "bidirectional+no_connect"))
    )
    (net (code "156") (name "unconnected-(IC40C-P4[3]{slash}EMC_A[3]-PadK9)") (class "Default")
      (node (ref "IC40") (pin "K9") (pinfunction "P4[3]/EMC_A[3]_K9") (pintype "bidirectional+no_connect"))
    )
    (net (code "157") (name "unconnected-(IC40C-P4[4]{slash}EMC_A[4]-PadP13)") (class "Default")
      (node (ref "IC40") (pin "P13") (pinfunction "P4[4]/EMC_A[4]_P13") (pintype "bidirectional+no_connect"))
    )
    (net (code "158") (name "unconnected-(IC40C-P4[5]{slash}EMC_A[5]-PadH10)") (class "Default")
      (node (ref "IC40") (pin "H10") (pinfunction "P4[5]/EMC_A[5]_H10") (pintype "bidirectional+no_connect"))
    )
    (net (code "159") (name "unconnected-(IC40C-P4[6]{slash}EMC_A[6]-PadK10)") (class "Default")
      (node (ref "IC40") (pin "K10") (pinfunction "P4[6]/EMC_A[6]_K10") (pintype "bidirectional+no_connect"))
    )
    (net (code "160") (name "unconnected-(IC40C-P4[7]{slash}EMC_A[7]-PadK12)") (class "Default")
      (node (ref "IC40") (pin "K12") (pinfunction "P4[7]/EMC_A[7]_K12") (pintype "bidirectional+no_connect"))
    )
    (net (code "161") (name "unconnected-(IC40C-P4[10]{slash}EMC_A[10]-PadG12)") (class "Default")
      (node (ref "IC40") (pin "G12") (pinfunction "P4[10]/EMC_A[10]_G12") (pintype "bidirectional+no_connect"))
    )
    (net (code "162") (name "unconnected-(IC40C-P4[14]{slash}EMC_A[14]-PadE8)") (class "Default")
      (node (ref "IC40") (pin "E8") (pinfunction "P4[14]/EMC_A[14]_E8") (pintype "bidirectional+no_connect"))
    )
    (net (code "163") (name "unconnected-(IC40C-P4[15]{slash}EMC_A[15]-PadC10)") (class "Default")
      (node (ref "IC40") (pin "C10") (pinfunction "P4[15]/EMC_A[15]_C10") (pintype "bidirectional+no_connect"))
    )
    (net (code "164") (name "unconnected-(IC40C-P4[16]{slash}EMC_A[16]-PadN12)") (class "Default")
      (node (ref "IC40") (pin "N12") (pinfunction "P4[16]/EMC_A[16]_N12") (pintype "bidirectional+no_connect"))
    )
    (net (code "165") (name "unconnected-(IC40C-P4[17]{slash}EMC_A[17]-PadN13)") (class "Default")
      (node (ref "IC40") (pin "N13") (pinfunction "P4[17]/EMC_A[17]_N13") (pintype "bidirectional+no_connect"))
    )
    (net (code "166") (name "unconnected-(IC40C-P4[18]{slash}EMC_A[18]-PadP14)") (class "Default")
      (node (ref "IC40") (pin "P14") (pinfunction "P4[18]/EMC_A[18]_P14") (pintype "bidirectional+no_connect"))
    )
    (net (code "167") (name "unconnected-(IC40C-P4[19]{slash}EMC_A[19]-PadM14)") (class "Default")
      (node (ref "IC40") (pin "M14") (pinfunction "P4[19]/EMC_A[19]_M14") (pintype "bidirectional+no_connect"))
    )
    (net (code "168") (name "unconnected-(IC40C-P4[24]{slash}~{EMC_OE}-PadC8)") (class "Default")
      (node (ref "IC40") (pin "C8") (pinfunction "P4[24]/~{EMC_OE}_C8") (pintype "bidirectional+no_connect"))
    )
    (net (code "169") (name "unconnected-(IC40C-P4[25]{slash}~{EMC_WE}-PadD9)") (class "Default")
      (node (ref "IC40") (pin "D9") (pinfunction "P4[25]/~{EMC_WE}_D9") (pintype "bidirectional+no_connect"))
    )
    (net (code "170") (name "unconnected-(IC40C-P4[27]{slash}~{EMC_BLS1}-PadF14)") (class "Default")
      (node (ref "IC40") (pin "F14") (pinfunction "P4[27]/~{EMC_BLS1}_F14") (pintype "bidirectional+no_connect"))
    )
    (net (code "171") (name "unconnected-(IC40C-P4[28]{slash}~{EMC_BLS2}{slash}U3_TXD{slash}T2_MAT0-PadD10)") (class "Default")
      (node (ref "IC40") (pin "D10") (pinfunction "P4[28]/~{EMC_BLS2}/U3_TXD/T2_MAT0_D10") (pintype "bidirectional+no_connect"))
    )
    (net (code "172") (name "unconnected-(IC40C-P4[29]{slash}~{EMC_BLS3}{slash}U3_RXD{slash}T2_MAT1{slash}I2C2_SCL-PadB9)") (class "Default")
      (node (ref "IC40") (pin "B9") (pinfunction "P4[29]/~{EMC_BLS3}/U3_RXD/T2_MAT1/I2C2_SCL_B9") (pintype "bidirectional+no_connect"))
    )
    (net (code "173") (name "unconnected-(IC40C-P4[30]{slash}~{EMC_CS0}-PadC7)") (class "Default")
      (node (ref "IC40") (pin "C7") (pinfunction "P4[30]/~{EMC_CS0}_C7") (pintype "bidirectional+no_connect"))
    )
    (net (code "174") (name "unconnected-(IC40C-P4[31]{slash}~{EMC_CS1}-PadE7)") (class "Default")
      (node (ref "IC40") (pin "E7") (pinfunction "P4[31]/~{EMC_CS1}_E7") (pintype "bidirectional+no_connect"))
    )
    (net (code "175") (name "unconnected-(IC40C-P5[1]{slash}EMC_A[25]{slash}SSP2_MISO{slash}T2_MAT3-PadH1)") (class "Default")
      (node (ref "IC40") (pin "H1") (pinfunction "P5[1]/EMC_A[25]/SSP2_MISO/T2_MAT3_H1") (pintype "bidirectional+no_connect"))
    )
    (net (code "176") (name "unconnected-(IC40C-P5[2]{slash}T3_MAT2{slash}I2C0_SDA-PadL12)") (class "Default")
      (node (ref "IC40") (pin "L12") (pinfunction "P5[2]/T3_MAT2/I2C0_SDA_L12") (pintype "bidirectional+no_connect"))
    )
    (net (code "177") (name "unconnected-(IC40C-P5[3]{slash}U4_RXD{slash}I2C0_SCL-PadG10)") (class "Default")
      (node (ref "IC40") (pin "G10") (pinfunction "P5[3]/U4_RXD/I2C0_SCL_G10") (pintype "bidirectional+no_connect"))
    )
    (net (code "178") (name "unconnected-(IC40C-P5[4]{slash}U0_OE{slash}T3_MAT3{slash}U4_TXD-PadC4)") (class "Default")
      (node (ref "IC40") (pin "C4") (pinfunction "P5[4]/U0_OE/T3_MAT3/U4_TXD_C4") (pintype "bidirectional+no_connect"))
    )
  )
)
